# bmsMaster_hvpath.net
KiCad netlist of a schematic drawn in Altium Designer
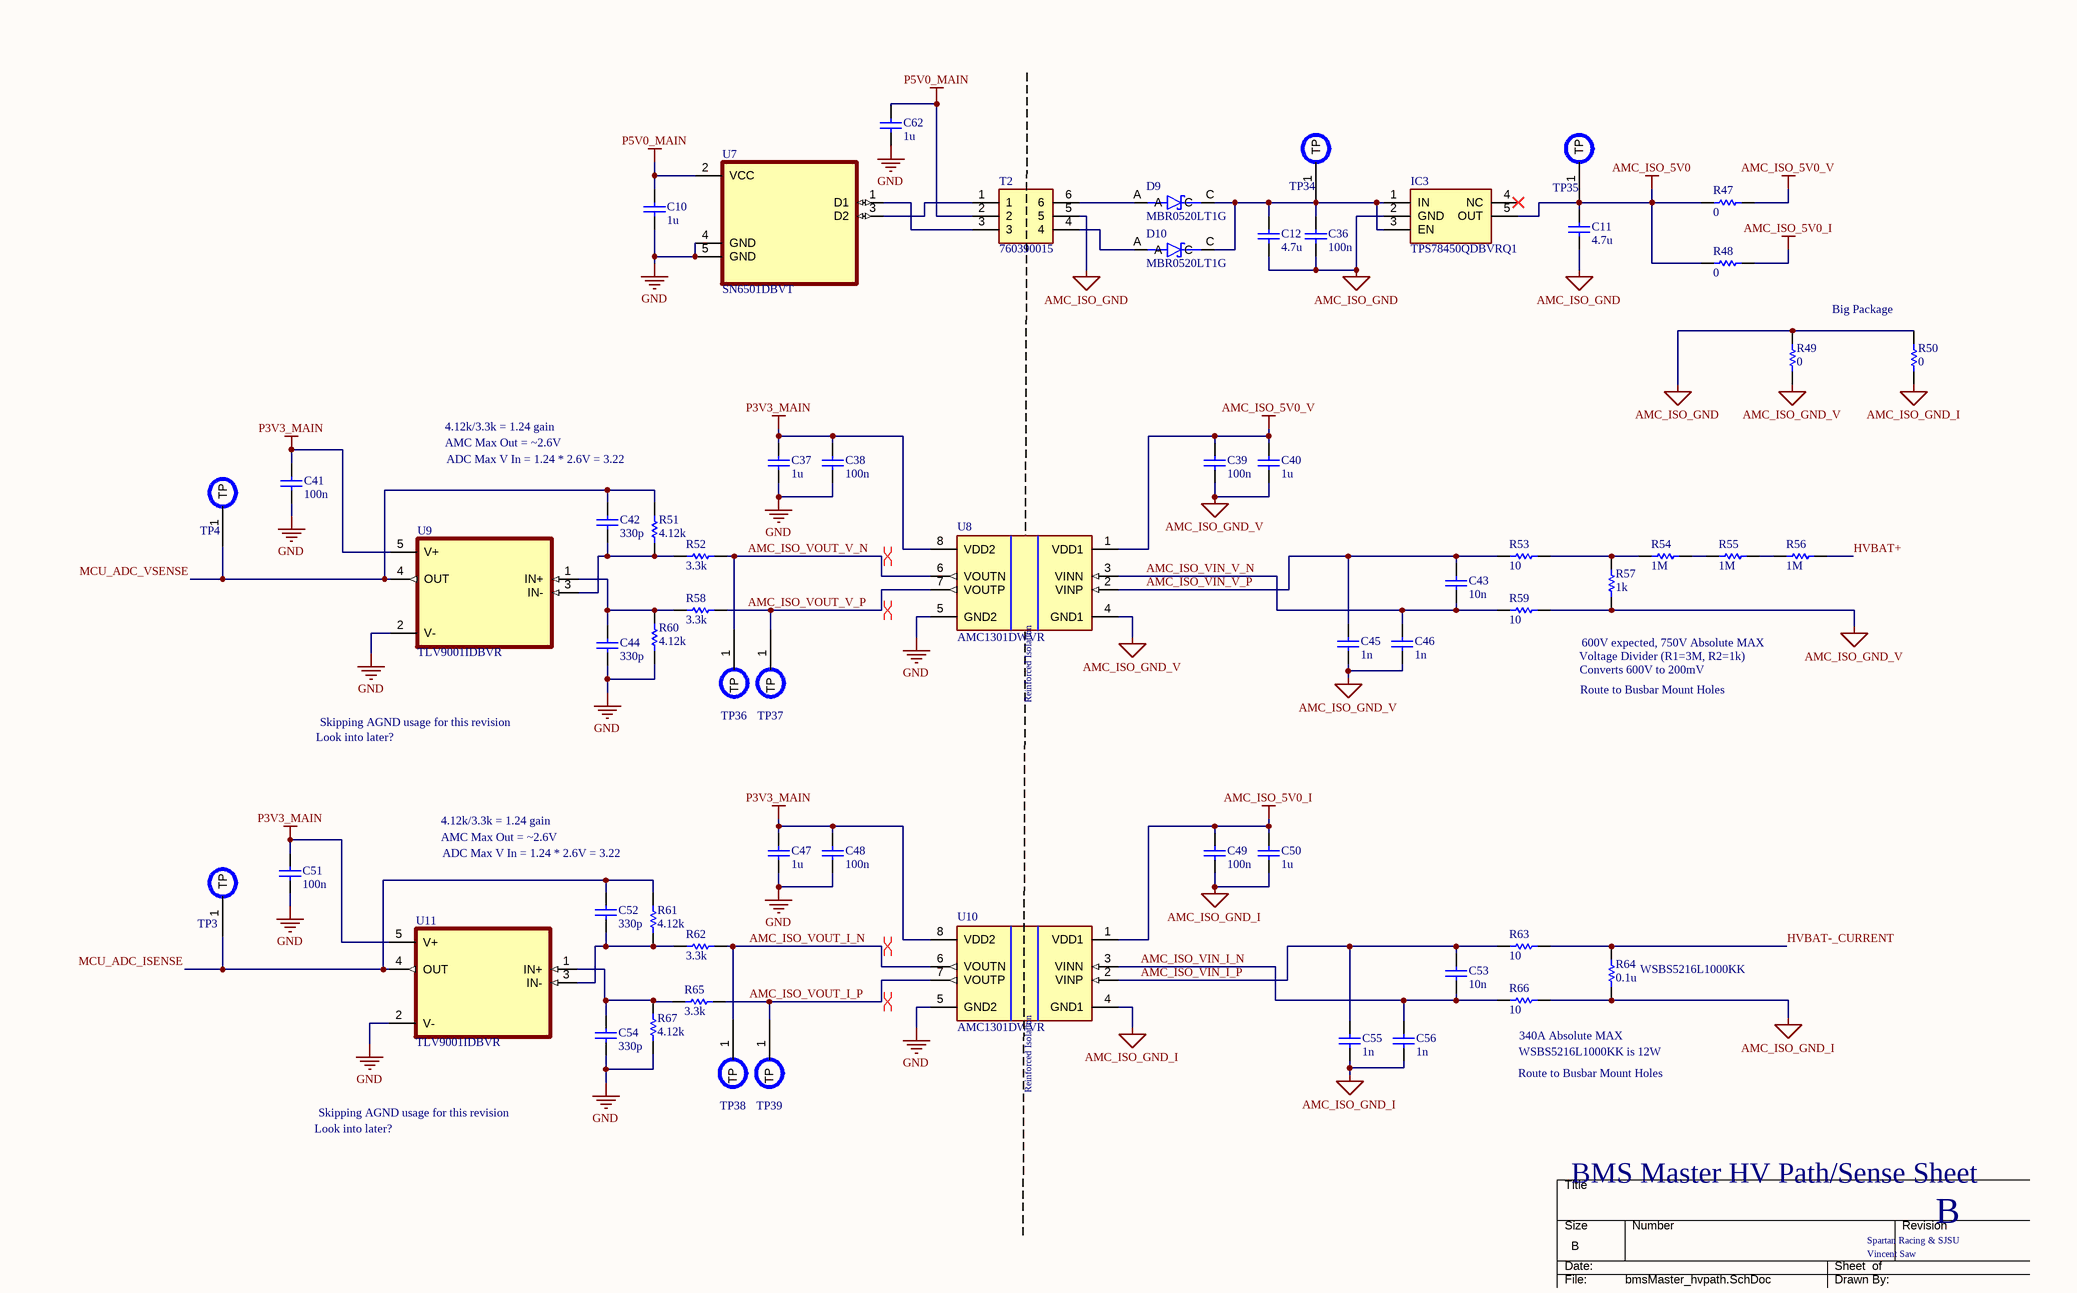
[diagram p0: bmsMaster_hvpath.SchDoc]

(export (version "E")
  (design (tool "Eeschema 10.0.6"))
  (components
    (comp (ref "C10")
      (value "1u")
      (footprint "CAPC1608X90N")
      (description "Capacitor")
      (libsource (lib "Simulation Generic Components") (part "Capacitor"))
    )
    (comp (ref "C11")
      (value "4.7u")
      (footprint "CAPC1608X90N")
      (description "Capacitor")
      (libsource (lib "Simulation Generic Components") (part "Capacitor"))
    )
    (comp (ref "C12")
      (value "4.7u")
      (footprint "CAPC1608X90N")
      (description "Capacitor")
      (libsource (lib "Simulation Generic Components") (part "Capacitor"))
    )
    (comp (ref "C36")
      (value "100n")
      (footprint "CAPC1608X90N")
      (description "Capacitor")
      (libsource (lib "Simulation Generic Components") (part "Capacitor"))
    )
    (comp (ref "C37")
      (value "1u")
      (footprint "CAPC1608X90N")
      (description "Capacitor")
      (libsource (lib "Simulation Generic Components") (part "Capacitor"))
    )
    (comp (ref "C38")
      (value "100n")
      (footprint "CAPC1608X90N")
      (description "Capacitor")
      (libsource (lib "Simulation Generic Components") (part "Capacitor"))
    )
    (comp (ref "C39")
      (value "100n")
      (footprint "CAPC1608X90N")
      (description "Capacitor")
      (libsource (lib "Simulation Generic Components") (part "Capacitor"))
    )
    (comp (ref "C40")
      (value "1u")
      (footprint "CAPC1608X90N")
      (description "Capacitor")
      (libsource (lib "Simulation Generic Components") (part "Capacitor"))
    )
    (comp (ref "C41")
      (value "100n")
      (footprint "CAPC1608X90N")
      (description "Capacitor")
      (libsource (lib "Simulation Generic Components") (part "Capacitor"))
    )
    (comp (ref "C42")
      (value "330p")
      (footprint "CAPC1608X90N")
      (description "Capacitor")
      (libsource (lib "Simulation Generic Components") (part "Capacitor"))
    )
    (comp (ref "C43")
      (value "10n")
      (footprint "CAPC1608X90N")
      (description "Capacitor")
      (libsource (lib "Simulation Generic Components") (part "Capacitor"))
    )
    (comp (ref "C44")
      (value "330p")
      (footprint "CAPC1608X90N")
      (description "Capacitor")
      (libsource (lib "Simulation Generic Components") (part "Capacitor"))
    )
    (comp (ref "C45")
      (value "1n")
      (footprint "CAPC1608X90N")
      (description "Capacitor")
      (libsource (lib "Simulation Generic Components") (part "Capacitor"))
    )
    (comp (ref "C46")
      (value "1n")
      (footprint "CAPC1608X90N")
      (description "Capacitor")
      (libsource (lib "Simulation Generic Components") (part "Capacitor"))
    )
    (comp (ref "C47")
      (value "1u")
      (footprint "CAPC1608X90N")
      (description "Capacitor")
      (libsource (lib "Simulation Generic Components") (part "Capacitor"))
    )
    (comp (ref "C48")
      (value "100n")
      (footprint "CAPC1608X90N")
      (description "Capacitor")
      (libsource (lib "Simulation Generic Components") (part "Capacitor"))
    )
    (comp (ref "C49")
      (value "100n")
      (footprint "CAPC1608X90N")
      (description "Capacitor")
      (libsource (lib "Simulation Generic Components") (part "Capacitor"))
    )
    (comp (ref "C50")
      (value "1u")
      (footprint "CAPC1608X90N")
      (description "Capacitor")
      (libsource (lib "Simulation Generic Components") (part "Capacitor"))
    )
    (comp (ref "C51")
      (value "100n")
      (footprint "CAPC1608X90N")
      (description "Capacitor")
      (libsource (lib "Simulation Generic Components") (part "Capacitor"))
    )
    (comp (ref "C52")
      (value "330p")
      (footprint "CAPC1608X90N")
      (description "Capacitor")
      (libsource (lib "Simulation Generic Components") (part "Capacitor"))
    )
    (comp (ref "C53")
      (value "10n")
      (footprint "CAPC1608X90N")
      (description "Capacitor")
      (libsource (lib "Simulation Generic Components") (part "Capacitor"))
    )
    (comp (ref "C54")
      (value "330p")
      (footprint "CAPC1608X90N")
      (description "Capacitor")
      (libsource (lib "Simulation Generic Components") (part "Capacitor"))
    )
    (comp (ref "C55")
      (value "1n")
      (footprint "CAPC1608X90N")
      (description "Capacitor")
      (libsource (lib "Simulation Generic Components") (part "Capacitor"))
    )
    (comp (ref "C56")
      (value "1n")
      (footprint "CAPC1608X90N")
      (description "Capacitor")
      (libsource (lib "Simulation Generic Components") (part "Capacitor"))
    )
    (comp (ref "C62")
      (value "1u")
      (footprint "CAPC1608X90N")
      (description "Capacitor")
      (libsource (lib "Simulation Generic Components") (part "Capacitor"))
    )
    (comp (ref "D9")
      (value "MBR0520LT1G")
      (footprint "MBR0520LT1G:SOD3716X135N")
      (description "Rectifier, Schottky Power; Plastic Sod-123; 0.5 a @ +90c If; +125; 20v; 1000")
      (fields (field (name "MF") "{'manufacturer': u'ON Semiconductor'}"))
      (libsource (lib "*") (part "MBR0520LT1G"))
    )
    (comp (ref "D10")
      (value "MBR0520LT1G")
      (footprint "MBR0520LT1G:SOD3716X135N")
      (description "Rectifier, Schottky Power; Plastic Sod-123; 0.5 a @ +90c If; +125; 20v; 1000")
      (fields (field (name "MF") "{'manufacturer': u'ON Semiconductor'}"))
      (libsource (lib "*") (part "MBR0520LT1G"))
    )
    (comp (ref "IC3")
      (value "TPS78450QDBVRQ1")
      (footprint "SamacSys:SOT95P280X145-5N")
      (description "Integrated Circuit")
      (fields (field (name "MOUSER PART NUMBER") "595-TPS78450QDBVRQ1"))
      (libsource (lib "*") (part "TPS78450QDBVRQ1"))
    )
    (comp (ref "R47")
      (value "0")
      (footprint "RESC1608X50N")
      (description "Resistor")
      (libsource (lib "Simulation Generic Components") (part "Resistor"))
    )
    (comp (ref "R48")
      (value "0")
      (footprint "RESC1608X50N")
      (description "Resistor")
      (libsource (lib "Simulation Generic Components") (part "Resistor"))
    )
    (comp (ref "R49")
      (value "0")
      (footprint "RESC1608X50N")
      (description "Resistor")
      (libsource (lib "Simulation Generic Components") (part "Resistor"))
    )
    (comp (ref "R50")
      (value "0")
      (footprint "RESC1608X50N")
      (description "Resistor")
      (libsource (lib "Simulation Generic Components") (part "Resistor"))
    )
    (comp (ref "R51")
      (value "4.12k")
      (footprint "RESC1608X50N")
      (description "Resistor")
      (libsource (lib "Simulation Generic Components") (part "Resistor"))
    )
    (comp (ref "R52")
      (value "3.3k")
      (footprint "RESC1608X50N")
      (description "Resistor")
      (libsource (lib "Simulation Generic Components") (part "Resistor"))
    )
    (comp (ref "R53")
      (value "10")
      (footprint "RESC1608X50N")
      (description "Resistor")
      (libsource (lib "Simulation Generic Components") (part "Resistor"))
    )
    (comp (ref "R54")
      (value "1M")
      (footprint "RESC1608X50N")
      (description "WSBS5216L1000KK")
      (fields (field (name "Comment") "Resistor"))
      (libsource (lib "Simulation Generic Components") (part "Resistor"))
    )
    (comp (ref "R55")
      (value "1M")
      (footprint "RESC1608X50N")
      (description "WSBS5216L1000KK")
      (fields (field (name "Comment") "Resistor"))
      (libsource (lib "Simulation Generic Components") (part "Resistor"))
    )
    (comp (ref "R56")
      (value "1M")
      (footprint "RESC1608X50N")
      (description "WSBS5216L1000KK")
      (fields (field (name "Comment") "Resistor"))
      (libsource (lib "Simulation Generic Components") (part "Resistor"))
    )
    (comp (ref "R57")
      (value "1k")
      (footprint "RESC1608X50N")
      (description "WSBS5216L1000KK")
      (fields (field (name "Comment") "Resistor"))
      (libsource (lib "Simulation Generic Components") (part "Resistor"))
    )
    (comp (ref "R58")
      (value "3.3k")
      (footprint "RESC1608X50N")
      (description "Resistor")
      (libsource (lib "Simulation Generic Components") (part "Resistor"))
    )
    (comp (ref "R59")
      (value "10")
      (footprint "RESC1608X50N")
      (description "Resistor")
      (libsource (lib "Simulation Generic Components") (part "Resistor"))
    )
    (comp (ref "R60")
      (value "4.12k")
      (footprint "RESC1608X50N")
      (description "Resistor")
      (libsource (lib "Simulation Generic Components") (part "Resistor"))
    )
    (comp (ref "R61")
      (value "4.12k")
      (footprint "RESC1608X50N")
      (description "Resistor")
      (libsource (lib "Simulation Generic Components") (part "Resistor"))
    )
    (comp (ref "R62")
      (value "3.3k")
      (footprint "RESC1608X50N")
      (description "Resistor")
      (libsource (lib "Simulation Generic Components") (part "Resistor"))
    )
    (comp (ref "R63")
      (value "10")
      (footprint "RESC1608X50N")
      (description "Resistor")
      (libsource (lib "Simulation Generic Components") (part "Resistor"))
    )
    (comp (ref "R64")
      (value "WSBS5216L1000KK")
      (footprint "RESC1608X50N")
      (fields (field (name "ALTIUM_VALUE") "0.1u"))
      (libsource (lib "Simulation Generic Components") (part "Resistor"))
    )
    (comp (ref "R65")
      (value "3.3k")
      (footprint "RESC1608X50N")
      (description "Resistor")
      (libsource (lib "Simulation Generic Components") (part "Resistor"))
    )
    (comp (ref "R66")
      (value "10")
      (footprint "RESC1608X50N")
      (description "Resistor")
      (libsource (lib "Simulation Generic Components") (part "Resistor"))
    )
    (comp (ref "R67")
      (value "4.12k")
      (footprint "RESC1608X50N")
      (description "Resistor")
      (libsource (lib "Simulation Generic Components") (part "Resistor"))
    )
    (comp (ref "T2")
      (value "760390015")
      (footprint "SamacSys:760390015")
      (description "Transformer")
      (fields (field (name "MOUSER PART NUMBER") "710-760390015"))
      (libsource (lib "*") (part "760390015"))
    )
    (comp (ref "TP3")
      (value "TSTPT")
      (footprint "Testpoint1")
      (libsource (lib "testpoint1") (part "Testpoint1"))
    )
    (comp (ref "TP4")
      (value "TSTPT")
      (footprint "Testpoint1")
      (libsource (lib "testpoint1") (part "Testpoint1"))
    )
    (comp (ref "TP34")
      (value "TSTPT")
      (footprint "Testpoint1")
      (libsource (lib "testpoint1") (part "Testpoint1"))
    )
    (comp (ref "TP35")
      (value "TSTPT")
      (footprint "Testpoint1")
      (libsource (lib "testpoint1") (part "Testpoint1"))
    )
    (comp (ref "TP36")
      (value "TSTPT")
      (footprint "Testpoint1")
      (libsource (lib "testpoint1") (part "Testpoint1"))
    )
    (comp (ref "TP37")
      (value "TSTPT")
      (footprint "Testpoint1")
      (libsource (lib "testpoint1") (part "Testpoint1"))
    )
    (comp (ref "TP38")
      (value "TSTPT")
      (footprint "Testpoint1")
      (libsource (lib "testpoint1") (part "Testpoint1"))
    )
    (comp (ref "TP39")
      (value "TSTPT")
      (footprint "Testpoint1")
      (libsource (lib "testpoint1") (part "Testpoint1"))
    )
    (comp (ref "U7")
      (value "SN6501DBVT")
      (footprint "SN6501DBVT:SOT95P280X145-5N")
      (fields (field (name "MF") "{'manufacturer': u'Texas Instruments'}"))
      (libsource (lib "*") (part "SN6501DBVT"))
    )
    (comp (ref "U8")
      (value "AMC1301DWVR")
      (footprint "SOIC127P1150X280-8N")
      (fields (field (name "MF") "{'manufacturer': u'Texas Instruments'}"))
      (libsource (lib "SnapEDA_Library") (part "AMC1301DWVR"))
    )
    (comp (ref "U9")
      (value "TLV9001IDBVR")
      (footprint "TLV9001IDBVR:SOT95P280X145-5N")
      (fields (field (name "MF") "{'manufacturer': u'Texas Instruments'}"))
      (libsource (lib "*") (part "TLV9001IDBVR"))
    )
    (comp (ref "U10")
      (value "AMC1301DWVR")
      (footprint "SOIC127P1150X280-8N")
      (fields (field (name "MF") "{'manufacturer': u'Texas Instruments'}"))
      (libsource (lib "SnapEDA_Library") (part "AMC1301DWVR"))
    )
    (comp (ref "U11")
      (value "TLV9001IDBVR")
      (footprint "TLV9001IDBVR:SOT95P280X145-5N")
      (fields (field (name "MF") "{'manufacturer': u'Texas Instruments'}"))
      (libsource (lib "*") (part "TLV9001IDBVR"))
    )
  )
  (nets
    (net (code "1") (name "/AMC_ISO_VIN_I_N") (class "Default")
      (node (ref "C53") (pin "1") (pinfunction "1_1") (pintype "passive"))
      (node (ref "C56") (pin "2") (pinfunction "2_2") (pintype "passive"))
      (node (ref "R66") (pin "2") (pinfunction "2_2") (pintype "passive"))
      (node (ref "U10") (pin "3") (pinfunction "VINN_3") (pintype "input"))
    )
    (net (code "2") (name "/AMC_ISO_VIN_I_P") (class "Default")
      (node (ref "C53") (pin "2") (pinfunction "2_2") (pintype "passive"))
      (node (ref "C55") (pin "2") (pinfunction "2_2") (pintype "passive"))
      (node (ref "R63") (pin "2") (pinfunction "2_2") (pintype "passive"))
      (node (ref "U10") (pin "2") (pinfunction "VINP_2") (pintype "input"))
    )
    (net (code "3") (name "/AMC_ISO_VIN_V_N") (class "Default")
      (node (ref "C43") (pin "1") (pinfunction "1_1") (pintype "passive"))
      (node (ref "C46") (pin "2") (pinfunction "2_2") (pintype "passive"))
      (node (ref "R59") (pin "2") (pinfunction "2_2") (pintype "passive"))
      (node (ref "U8") (pin "3") (pinfunction "VINN_3") (pintype "input"))
    )
    (net (code "4") (name "/AMC_ISO_VIN_V_P") (class "Default")
      (node (ref "C43") (pin "2") (pinfunction "2_2") (pintype "passive"))
      (node (ref "C45") (pin "2") (pinfunction "2_2") (pintype "passive"))
      (node (ref "R53") (pin "2") (pinfunction "2_2") (pintype "passive"))
      (node (ref "U8") (pin "2") (pinfunction "VINP_2") (pintype "input"))
    )
    (net (code "5") (name "/AMC_ISO_VOUT_I_N") (class "Default")
      (node (ref "R62") (pin "1") (pinfunction "1_1") (pintype "passive"))
      (node (ref "TP38") (pin "1") (pinfunction "TP_1") (pintype "passive"))
      (node (ref "U10") (pin "6") (pinfunction "VOUTN_6") (pintype "output"))
    )
    (net (code "6") (name "/AMC_ISO_VOUT_I_P") (class "Default")
      (node (ref "R65") (pin "1") (pinfunction "1_1") (pintype "passive"))
      (node (ref "TP39") (pin "1") (pinfunction "TP_1") (pintype "passive"))
      (node (ref "U10") (pin "7") (pinfunction "VOUTP_7") (pintype "output"))
    )
    (net (code "7") (name "/AMC_ISO_VOUT_V_N") (class "Default")
      (node (ref "R52") (pin "1") (pinfunction "1_1") (pintype "passive"))
      (node (ref "TP36") (pin "1") (pinfunction "TP_1") (pintype "passive"))
      (node (ref "U8") (pin "6") (pinfunction "VOUTN_6") (pintype "output"))
    )
    (net (code "8") (name "/AMC_ISO_VOUT_V_P") (class "Default")
      (node (ref "R58") (pin "1") (pinfunction "1_1") (pintype "passive"))
      (node (ref "TP37") (pin "1") (pinfunction "TP_1") (pintype "passive"))
      (node (ref "U8") (pin "7") (pinfunction "VOUTP_7") (pintype "output"))
    )
    (net (code "9") (name "/HVBAT+") (class "Default")
      (node (ref "R56") (pin "1") (pinfunction "1_1") (pintype "passive"))
    )
    (net (code "10") (name "/HVBAT-_CURRENT") (class "Default")
      (node (ref "R63") (pin "1") (pinfunction "1_1") (pintype "passive"))
      (node (ref "R64") (pin "2") (pinfunction "2_2") (pintype "passive"))
    )
    (net (code "11") (name "/MCU_ADC_ISENSE") (class "Default")
      (node (ref "C52") (pin "2") (pinfunction "2_2") (pintype "passive"))
      (node (ref "R61") (pin "1") (pinfunction "1_1") (pintype "passive"))
      (node (ref "TP3") (pin "1") (pinfunction "TP_1") (pintype "passive"))
      (node (ref "U11") (pin "4") (pinfunction "OUT_4") (pintype "output"))
    )
    (net (code "12") (name "/MCU_ADC_VSENSE") (class "Default")
      (node (ref "C42") (pin "2") (pinfunction "2_2") (pintype "passive"))
      (node (ref "R51") (pin "1") (pinfunction "1_1") (pintype "passive"))
      (node (ref "TP4") (pin "1") (pinfunction "TP_1") (pintype "passive"))
      (node (ref "U9") (pin "4") (pinfunction "OUT_4") (pintype "output"))
    )
    (net (code "13") (name "AMC_ISO_5V0") (class "Default")
      (node (ref "C11") (pin "2") (pinfunction "2_2") (pintype "passive"))
      (node (ref "IC3") (pin "5") (pinfunction "OUT_5") (pintype "passive"))
      (node (ref "R47") (pin "1") (pinfunction "1_1") (pintype "passive"))
      (node (ref "R48") (pin "1") (pinfunction "1_1") (pintype "passive"))
      (node (ref "TP35") (pin "1") (pinfunction "TP_1") (pintype "passive"))
    )
    (net (code "14") (name "AMC_ISO_5V0_I") (class "Default")
      (node (ref "C49") (pin "2") (pinfunction "2_2") (pintype "passive"))
      (node (ref "C50") (pin "2") (pinfunction "2_2") (pintype "passive"))
      (node (ref "R48") (pin "2") (pinfunction "2_2") (pintype "passive"))
      (node (ref "U10") (pin "1") (pinfunction "VDD1_1") (pintype "power_in"))
    )
    (net (code "15") (name "AMC_ISO_5V0_V") (class "Default")
      (node (ref "C39") (pin "2") (pinfunction "2_2") (pintype "passive"))
      (node (ref "C40") (pin "2") (pinfunction "2_2") (pintype "passive"))
      (node (ref "R47") (pin "2") (pinfunction "2_2") (pintype "passive"))
      (node (ref "U8") (pin "1") (pinfunction "VDD1_1") (pintype "power_in"))
    )
    (net (code "16") (name "AMC_ISO_GND") (class "Default")
      (node (ref "C11") (pin "1") (pinfunction "1_1") (pintype "passive"))
      (node (ref "C12") (pin "1") (pinfunction "1_1") (pintype "passive"))
      (node (ref "C36") (pin "1") (pinfunction "1_1") (pintype "passive"))
      (node (ref "IC3") (pin "2") (pinfunction "GND_2") (pintype "passive"))
      (node (ref "R49") (pin "2") (pinfunction "2_2") (pintype "passive"))
      (node (ref "R50") (pin "2") (pinfunction "2_2") (pintype "passive"))
      (node (ref "T2") (pin "5") (pinfunction "5_5") (pintype "passive"))
    )
    (net (code "17") (name "AMC_ISO_GND_I") (class "Default")
      (node (ref "C49") (pin "1") (pinfunction "1_1") (pintype "passive"))
      (node (ref "C50") (pin "1") (pinfunction "1_1") (pintype "passive"))
      (node (ref "C55") (pin "1") (pinfunction "1_1") (pintype "passive"))
      (node (ref "C56") (pin "1") (pinfunction "1_1") (pintype "passive"))
      (node (ref "R50") (pin "1") (pinfunction "1_1") (pintype "passive"))
      (node (ref "R64") (pin "1") (pinfunction "1_1") (pintype "passive"))
      (node (ref "R66") (pin "1") (pinfunction "1_1") (pintype "passive"))
      (node (ref "U10") (pin "4") (pinfunction "GND1_4") (pintype "power_in"))
    )
    (net (code "18") (name "AMC_ISO_GND_V") (class "Default")
      (node (ref "C39") (pin "1") (pinfunction "1_1") (pintype "passive"))
      (node (ref "C40") (pin "1") (pinfunction "1_1") (pintype "passive"))
      (node (ref "C45") (pin "1") (pinfunction "1_1") (pintype "passive"))
      (node (ref "C46") (pin "1") (pinfunction "1_1") (pintype "passive"))
      (node (ref "R49") (pin "1") (pinfunction "1_1") (pintype "passive"))
      (node (ref "R57") (pin "1") (pinfunction "1_1") (pintype "passive"))
      (node (ref "R59") (pin "1") (pinfunction "1_1") (pintype "passive"))
      (node (ref "U8") (pin "4") (pinfunction "GND1_4") (pintype "power_in"))
    )
    (net (code "19") (name "GND") (class "Default")
      (node (ref "C10") (pin "1") (pinfunction "1_1") (pintype "passive"))
      (node (ref "C37") (pin "1") (pinfunction "1_1") (pintype "passive"))
      (node (ref "C38") (pin "1") (pinfunction "1_1") (pintype "passive"))
      (node (ref "C41") (pin "1") (pinfunction "1_1") (pintype "passive"))
      (node (ref "C44") (pin "1") (pinfunction "1_1") (pintype "passive"))
      (node (ref "C47") (pin "1") (pinfunction "1_1") (pintype "passive"))
      (node (ref "C48") (pin "1") (pinfunction "1_1") (pintype "passive"))
      (node (ref "C51") (pin "1") (pinfunction "1_1") (pintype "passive"))
      (node (ref "C54") (pin "1") (pinfunction "1_1") (pintype "passive"))
      (node (ref "C62") (pin "1") (pinfunction "1_1") (pintype "passive"))
      (node (ref "R60") (pin "2") (pinfunction "2_2") (pintype "passive"))
      (node (ref "R67") (pin "2") (pinfunction "2_2") (pintype "passive"))
      (node (ref "U10") (pin "5") (pinfunction "GND2_5") (pintype "power_in"))
      (node (ref "U11") (pin "2") (pinfunction "V-_2") (pintype "power_in"))
      (node (ref "U7") (pin "4") (pinfunction "GND_4") (pintype "power_in"))
      (node (ref "U7") (pin "5") (pinfunction "GND_5") (pintype "power_in"))
      (node (ref "U8") (pin "5") (pinfunction "GND2_5") (pintype "power_in"))
      (node (ref "U9") (pin "2") (pinfunction "V-_2") (pintype "power_in"))
    )
    (net (code "20") (name "Net-(D9-PadA)") (class "Default")
      (node (ref "D9") (pin "A") (pinfunction "A_A") (pintype "passive"))
      (node (ref "T2") (pin "6") (pinfunction "6_6") (pintype "passive"))
    )
    (net (code "21") (name "Net-(D10-PadA)") (class "Default")
      (node (ref "D10") (pin "A") (pinfunction "A_A") (pintype "passive"))
      (node (ref "T2") (pin "4") (pinfunction "4_4") (pintype "passive"))
    )
    (net (code "22") (name "Net-(IC3-EN)") (class "Default")
      (node (ref "C12") (pin "2") (pinfunction "2_2") (pintype "passive"))
      (node (ref "C36") (pin "2") (pinfunction "2_2") (pintype "passive"))
      (node (ref "D10") (pin "C") (pinfunction "C_C") (pintype "passive"))
      (node (ref "D9") (pin "C") (pinfunction "C_C") (pintype "passive"))
      (node (ref "IC3") (pin "1") (pinfunction "IN_1") (pintype "passive"))
      (node (ref "IC3") (pin "3") (pinfunction "EN_3") (pintype "passive"))
      (node (ref "TP34") (pin "1") (pinfunction "TP_1") (pintype "passive"))
    )
    (net (code "23") (name "Net-(R53-Pad1)") (class "Default")
      (node (ref "R53") (pin "1") (pinfunction "1_1") (pintype "passive"))
      (node (ref "R54") (pin "2") (pinfunction "2_2") (pintype "passive"))
      (node (ref "R57") (pin "2") (pinfunction "2_2") (pintype "passive"))
    )
    (net (code "24") (name "Net-(R54-Pad1)") (class "Default")
      (node (ref "R54") (pin "1") (pinfunction "1_1") (pintype "passive"))
      (node (ref "R55") (pin "2") (pinfunction "2_2") (pintype "passive"))
    )
    (net (code "25") (name "Net-(R55-Pad1)") (class "Default")
      (node (ref "R55") (pin "1") (pinfunction "1_1") (pintype "passive"))
      (node (ref "R56") (pin "2") (pinfunction "2_2") (pintype "passive"))
    )
    (net (code "26") (name "Net-(U7-D1)") (class "Default")
      (node (ref "T2") (pin "3") (pinfunction "3_3") (pintype "passive"))
      (node (ref "U7") (pin "1") (pinfunction "D1_1") (pintype "bidirectional"))
    )
    (net (code "27") (name "Net-(U7-D2)") (class "Default")
      (node (ref "T2") (pin "1") (pinfunction "1_1") (pintype "passive"))
      (node (ref "U7") (pin "3") (pinfunction "D2_3") (pintype "bidirectional"))
    )
    (net (code "28") (name "Net-(U9-IN+)") (class "Default")
      (node (ref "C44") (pin "2") (pinfunction "2_2") (pintype "passive"))
      (node (ref "R58") (pin "2") (pinfunction "2_2") (pintype "passive"))
      (node (ref "R60") (pin "1") (pinfunction "1_1") (pintype "passive"))
      (node (ref "U9") (pin "1") (pinfunction "IN+_1") (pintype "input"))
    )
    (net (code "29") (name "Net-(U9-IN-)") (class "Default")
      (node (ref "C42") (pin "1") (pinfunction "1_1") (pintype "passive"))
      (node (ref "R51") (pin "2") (pinfunction "2_2") (pintype "passive"))
      (node (ref "R52") (pin "2") (pinfunction "2_2") (pintype "passive"))
      (node (ref "U9") (pin "3") (pinfunction "IN-_3") (pintype "input"))
    )
    (net (code "30") (name "Net-(U11-IN+)") (class "Default")
      (node (ref "C54") (pin "2") (pinfunction "2_2") (pintype "passive"))
      (node (ref "R65") (pin "2") (pinfunction "2_2") (pintype "passive"))
      (node (ref "R67") (pin "1") (pinfunction "1_1") (pintype "passive"))
      (node (ref "U11") (pin "1") (pinfunction "IN+_1") (pintype "input"))
    )
    (net (code "31") (name "Net-(U11-IN-)") (class "Default")
      (node (ref "C52") (pin "1") (pinfunction "1_1") (pintype "passive"))
      (node (ref "R61") (pin "2") (pinfunction "2_2") (pintype "passive"))
      (node (ref "R62") (pin "2") (pinfunction "2_2") (pintype "passive"))
      (node (ref "U11") (pin "3") (pinfunction "IN-_3") (pintype "input"))
    )
    (net (code "32") (name "P3V3_MAIN") (class "Default")
      (node (ref "C37") (pin "2") (pinfunction "2_2") (pintype "passive"))
      (node (ref "C38") (pin "2") (pinfunction "2_2") (pintype "passive"))
      (node (ref "C41") (pin "2") (pinfunction "2_2") (pintype "passive"))
      (node (ref "C47") (pin "2") (pinfunction "2_2") (pintype "passive"))
      (node (ref "C48") (pin "2") (pinfunction "2_2") (pintype "passive"))
      (node (ref "C51") (pin "2") (pinfunction "2_2") (pintype "passive"))
      (node (ref "U10") (pin "8") (pinfunction "VDD2_8") (pintype "power_in"))
      (node (ref "U11") (pin "5") (pinfunction "V+_5") (pintype "power_in"))
      (node (ref "U8") (pin "8") (pinfunction "VDD2_8") (pintype "power_in"))
      (node (ref "U9") (pin "5") (pinfunction "V+_5") (pintype "power_in"))
    )
    (net (code "33") (name "P5V0_MAIN") (class "Default")
      (node (ref "C10") (pin "2") (pinfunction "2_2") (pintype "passive"))
      (node (ref "C62") (pin "2") (pinfunction "2_2") (pintype "passive"))
      (node (ref "T2") (pin "2") (pinfunction "2_2") (pintype "passive"))
      (node (ref "U7") (pin "2") (pinfunction "VCC_2") (pintype "power_in"))
    )
    (net (code "34") (name "unconnected-(IC3-NC-Pad4)") (class "Default")
      (node (ref "IC3") (pin "4") (pinfunction "NC_4") (pintype "passive+no_connect"))
    )
  )
)
